# PlantModule.net
KiCad netlist of a schematic drawn in EAGLE
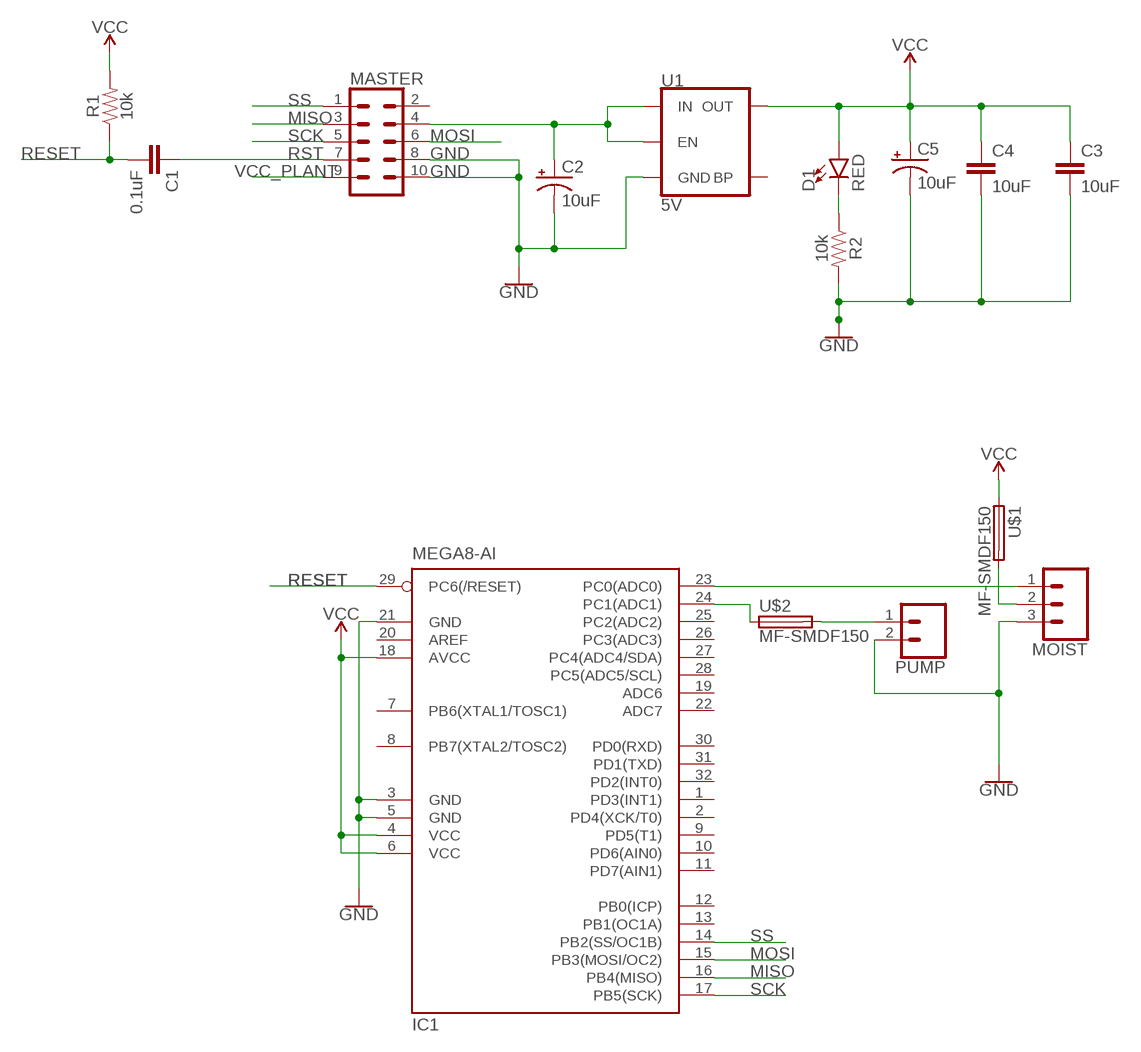
[diagram p0: schematic, sheet 1]

(export (version "E")
  (design (tool "Eeschema 10.0.6"))
  (components
    (comp (ref "C1")
      (value "0.1uF")
      (footprint "eagle-import:0402")
      (libsource (lib "eagle-import") (part "0.1UF-0402-16V-10%"))
    )
    (comp (ref "C2")
      (value "10uF")
      (footprint "eagle-import:EIA3216")
      (libsource (lib "eagle-import") (part "10UF-POLAR-EIA3216-16V-10%(TANT)"))
    )
    (comp (ref "C3")
      (value "10uF")
      (footprint "eagle-import:0603")
      (libsource (lib "eagle-import") (part "10UF-0603-6.3V-20%"))
    )
    (comp (ref "C4")
      (value "10uF")
      (footprint "eagle-import:0603")
      (libsource (lib "eagle-import") (part "10UF-0603-6.3V-20%"))
    )
    (comp (ref "C5")
      (value "10uF")
      (footprint "eagle-import:0603-POLAR")
      (libsource (lib "eagle-import") (part "10UF-POLAR-0603-6.3V-20%(TANT)"))
    )
    (comp (ref "D1")
      (value "RED")
      (footprint "eagle-import:LED-0603")
      (libsource (lib "eagle-import") (part "LED-RED0603"))
    )
    (comp (ref "IC1")
      (value "MEGA8-AI")
      (footprint "eagle-import:TQFP32-08")
      (fields (field (name "MPN") "ATMEGA8-16AU"))
      (libsource (lib "eagle-import") (part "MEGA8-AI"))
    )
    (comp (ref "MASTER")
      (value "CONN_05X2SHD")
      (footprint "eagle-import:2X5-SHROUDED")
      (libsource (lib "eagle-import") (part "CONN_05X2SHD"))
    )
    (comp (ref "MOIST")
      (value "CONN_03")
      (footprint "eagle-import:1X03")
      (libsource (lib "eagle-import") (part "CONN_03"))
    )
    (comp (ref "PUMP")
      (value "CONN_02")
      (footprint "eagle-import:1X02")
      (libsource (lib "eagle-import") (part "CONN_02"))
    )
    (comp (ref "R1")
      (value "10k")
      (footprint "eagle-import:0603")
      (libsource (lib "eagle-import") (part "10KOHM-0603-1/10W-1%"))
    )
    (comp (ref "R2")
      (value "10k")
      (footprint "eagle-import:0603")
      (libsource (lib "eagle-import") (part "10KOHM-0603-1/10W-1%"))
    )
    (comp (ref "U$1")
      (value "MF-SMDF150")
      (footprint "eagle-import:MF-SMDF050")
      (libsource (lib "eagle-import") (part "MF-SMDF150"))
    )
    (comp (ref "U$2")
      (value "MF-SMDF150")
      (footprint "eagle-import:MF-SMDF050")
      (libsource (lib "eagle-import") (part "MF-SMDF150"))
    )
    (comp (ref "U1")
      (value "5V")
      (footprint "eagle-import:SOT23-5")
      (libsource (lib "eagle-import") (part "V_REG_MIC52055V"))
    )
  )
  (nets
    (net (code "1") (name "/MISO") (class "Default")
      (node (ref "IC1") (pin "16") (pinfunction "PB4(MISO)_16") (pintype "bidirectional"))
      (node (ref "MASTER") (pin "3") (pinfunction "3_3") (pintype "passive"))
    )
    (net (code "2") (name "/MOSI") (class "Default")
      (node (ref "IC1") (pin "15") (pinfunction "PB3(MOSI/OC2)_15") (pintype "bidirectional"))
      (node (ref "MASTER") (pin "6") (pinfunction "6_6") (pintype "passive"))
    )
    (net (code "3") (name "/RESET") (class "Default")
      (node (ref "C1") (pin "2") (pinfunction "2_2") (pintype "passive"))
      (node (ref "IC1") (pin "29") (pinfunction "PC6(/RESET)_29") (pintype "bidirectional"))
      (node (ref "R1") (pin "1") (pinfunction "1_1") (pintype "passive"))
    )
    (net (code "4") (name "/RST") (class "Default")
      (node (ref "C1") (pin "1") (pinfunction "1_1") (pintype "passive"))
      (node (ref "MASTER") (pin "7") (pinfunction "7_7") (pintype "passive"))
    )
    (net (code "5") (name "/SCK") (class "Default")
      (node (ref "IC1") (pin "17") (pinfunction "PB5(SCK)_17") (pintype "bidirectional"))
      (node (ref "MASTER") (pin "5") (pinfunction "5_5") (pintype "passive"))
    )
    (net (code "6") (name "/SS") (class "Default")
      (node (ref "IC1") (pin "14") (pinfunction "PB2(SS/OC1B)_14") (pintype "bidirectional"))
      (node (ref "MASTER") (pin "1") (pinfunction "1_1") (pintype "passive"))
    )
    (net (code "7") (name "/VCC_PLANT") (class "Default")
      (node (ref "MASTER") (pin "9") (pinfunction "9_9") (pintype "passive"))
    )
    (net (code "8") (name "GND") (class "Default")
      (node (ref "C2") (pin "-") (pinfunction "-_-") (pintype "passive"))
      (node (ref "C3") (pin "2") (pinfunction "2_2") (pintype "passive"))
      (node (ref "C4") (pin "2") (pinfunction "2_2") (pintype "passive"))
      (node (ref "C5") (pin "-") (pinfunction "-_-") (pintype "passive"))
      (node (ref "IC1") (pin "21") (pinfunction "GND_21") (pintype "power_in"))
      (node (ref "IC1") (pin "3") (pinfunction "GND_3") (pintype "power_in"))
      (node (ref "IC1") (pin "5") (pinfunction "GND_5") (pintype "power_in"))
      (node (ref "MASTER") (pin "10") (pinfunction "10_10") (pintype "passive"))
      (node (ref "MASTER") (pin "8") (pinfunction "8_8") (pintype "passive"))
      (node (ref "MOIST") (pin "3") (pinfunction "3_3") (pintype "passive"))
      (node (ref "PUMP") (pin "2") (pinfunction "2_2") (pintype "passive"))
      (node (ref "R2") (pin "2") (pinfunction "2_2") (pintype "passive"))
      (node (ref "U1") (pin "2") (pinfunction "GND_2") (pintype "input"))
    )
    (net (code "9") (name "Net-(D1-PadC)") (class "Default")
      (node (ref "D1") (pin "C") (pinfunction "C_C") (pintype "passive"))
      (node (ref "R2") (pin "1") (pinfunction "1_1") (pintype "passive"))
    )
    (net (code "10") (name "Net-(IC1-PC0(ADC0))") (class "Default")
      (node (ref "IC1") (pin "23") (pinfunction "PC0(ADC0)_23") (pintype "bidirectional"))
      (node (ref "MOIST") (pin "1") (pinfunction "1_1") (pintype "passive"))
    )
    (net (code "11") (name "Net-(IC1-PC1(ADC1))") (class "Default")
      (node (ref "IC1") (pin "24") (pinfunction "PC1(ADC1)_24") (pintype "bidirectional"))
      (node (ref "U$2") (pin "1") (pinfunction "1_1") (pintype "passive"))
    )
    (net (code "12") (name "Net-(MOIST-Pad2)") (class "Default")
      (node (ref "MOIST") (pin "2") (pinfunction "2_2") (pintype "passive"))
      (node (ref "U$1") (pin "2") (pinfunction "2_2") (pintype "passive"))
    )
    (net (code "13") (name "Net-(PUMP-Pad1)") (class "Default")
      (node (ref "PUMP") (pin "1") (pinfunction "1_1") (pintype "passive"))
      (node (ref "U$2") (pin "2") (pinfunction "2_2") (pintype "passive"))
    )
    (net (code "14") (name "Net-(U1-EN)") (class "Default")
      (node (ref "C2") (pin "+") (pinfunction "+_+") (pintype "passive"))
      (node (ref "MASTER") (pin "4") (pinfunction "4_4") (pintype "passive"))
      (node (ref "U1") (pin "1") (pinfunction "IN_1") (pintype "input"))
      (node (ref "U1") (pin "3") (pinfunction "EN_3") (pintype "input"))
    )
    (net (code "15") (name "VCC") (class "Default")
      (node (ref "C3") (pin "1") (pinfunction "1_1") (pintype "passive"))
      (node (ref "C4") (pin "1") (pinfunction "1_1") (pintype "passive"))
      (node (ref "C5") (pin "+") (pinfunction "+_+") (pintype "passive"))
      (node (ref "D1") (pin "A") (pinfunction "A_A") (pintype "passive"))
      (node (ref "IC1") (pin "18") (pinfunction "AVCC_18") (pintype "power_in"))
      (node (ref "IC1") (pin "4") (pinfunction "VCC_4") (pintype "power_in"))
      (node (ref "IC1") (pin "6") (pinfunction "VCC_6") (pintype "power_in"))
      (node (ref "R1") (pin "2") (pinfunction "2_2") (pintype "passive"))
      (node (ref "U$1") (pin "1") (pinfunction "1_1") (pintype "passive"))
      (node (ref "U1") (pin "5") (pinfunction "OUT_5") (pintype "passive"))
    )
    (net (code "16") (name "unconnected-(IC1-ADC6-Pad19)") (class "Default")
      (node (ref "IC1") (pin "19") (pinfunction "ADC6_19") (pintype "bidirectional"))
    )
    (net (code "17") (name "unconnected-(IC1-ADC7-Pad22)") (class "Default")
      (node (ref "IC1") (pin "22") (pinfunction "ADC7_22") (pintype "bidirectional"))
    )
    (net (code "18") (name "unconnected-(IC1-AREF-Pad20)") (class "Default")
      (node (ref "IC1") (pin "20") (pinfunction "AREF_20") (pintype "passive"))
    )
    (net (code "19") (name "unconnected-(IC1-PB0(ICP)-Pad12)") (class "Default")
      (node (ref "IC1") (pin "12") (pinfunction "PB0(ICP)_12") (pintype "bidirectional"))
    )
    (net (code "20") (name "unconnected-(IC1-PB1(OC1A)-Pad13)") (class "Default")
      (node (ref "IC1") (pin "13") (pinfunction "PB1(OC1A)_13") (pintype "bidirectional"))
    )
    (net (code "21") (name "unconnected-(IC1-PB6(XTAL1{slash}TOSC1)-Pad7)") (class "Default")
      (node (ref "IC1") (pin "7") (pinfunction "PB6(XTAL1/TOSC1)_7") (pintype "bidirectional"))
    )
    (net (code "22") (name "unconnected-(IC1-PB7(XTAL2{slash}TOSC2)-Pad8)") (class "Default")
      (node (ref "IC1") (pin "8") (pinfunction "PB7(XTAL2/TOSC2)_8") (pintype "bidirectional"))
    )
    (net (code "23") (name "unconnected-(IC1-PC2(ADC2)-Pad25)") (class "Default")
      (node (ref "IC1") (pin "25") (pinfunction "PC2(ADC2)_25") (pintype "bidirectional"))
    )
    (net (code "24") (name "unconnected-(IC1-PC3(ADC3)-Pad26)") (class "Default")
      (node (ref "IC1") (pin "26") (pinfunction "PC3(ADC3)_26") (pintype "bidirectional"))
    )
    (net (code "25") (name "unconnected-(IC1-PC4(ADC4{slash}SDA)-Pad27)") (class "Default")
      (node (ref "IC1") (pin "27") (pinfunction "PC4(ADC4/SDA)_27") (pintype "bidirectional"))
    )
    (net (code "26") (name "unconnected-(IC1-PC5(ADC5{slash}SCL)-Pad28)") (class "Default")
      (node (ref "IC1") (pin "28") (pinfunction "PC5(ADC5/SCL)_28") (pintype "bidirectional"))
    )
    (net (code "27") (name "unconnected-(IC1-PD0(RXD)-Pad30)") (class "Default")
      (node (ref "IC1") (pin "30") (pinfunction "PD0(RXD)_30") (pintype "bidirectional"))
    )
    (net (code "28") (name "unconnected-(IC1-PD1(TXD)-Pad31)") (class "Default")
      (node (ref "IC1") (pin "31") (pinfunction "PD1(TXD)_31") (pintype "bidirectional"))
    )
    (net (code "29") (name "unconnected-(IC1-PD2(INT0)-Pad32)") (class "Default")
      (node (ref "IC1") (pin "32") (pinfunction "PD2(INT0)_32") (pintype "bidirectional"))
    )
    (net (code "30") (name "unconnected-(IC1-PD3(INT1)-Pad1)") (class "Default")
      (node (ref "IC1") (pin "1") (pinfunction "PD3(INT1)_1") (pintype "bidirectional"))
    )
    (net (code "31") (name "unconnected-(IC1-PD4(XCK{slash}T0)-Pad2)") (class "Default")
      (node (ref "IC1") (pin "2") (pinfunction "PD4(XCK/T0)_2") (pintype "bidirectional"))
    )
    (net (code "32") (name "unconnected-(IC1-PD5(T1)-Pad9)") (class "Default")
      (node (ref "IC1") (pin "9") (pinfunction "PD5(T1)_9") (pintype "bidirectional"))
    )
    (net (code "33") (name "unconnected-(IC1-PD6(AIN0)-Pad10)") (class "Default")
      (node (ref "IC1") (pin "10") (pinfunction "PD6(AIN0)_10") (pintype "bidirectional"))
    )
    (net (code "34") (name "unconnected-(IC1-PD7(AIN1)-Pad11)") (class "Default")
      (node (ref "IC1") (pin "11") (pinfunction "PD7(AIN1)_11") (pintype "bidirectional"))
    )
    (net (code "35") (name "unconnected-(MASTER-Pad2)") (class "Default")
      (node (ref "MASTER") (pin "2") (pinfunction "2_2") (pintype "passive"))
    )
    (net (code "36") (name "unconnected-(U1-BP-Pad4)") (class "Default")
      (node (ref "U1") (pin "4") (pinfunction "BP_4") (pintype "input"))
    )
  )
)
